# TRC1_0_0.net
KiCad netlist of a schematic drawn in EAGLE
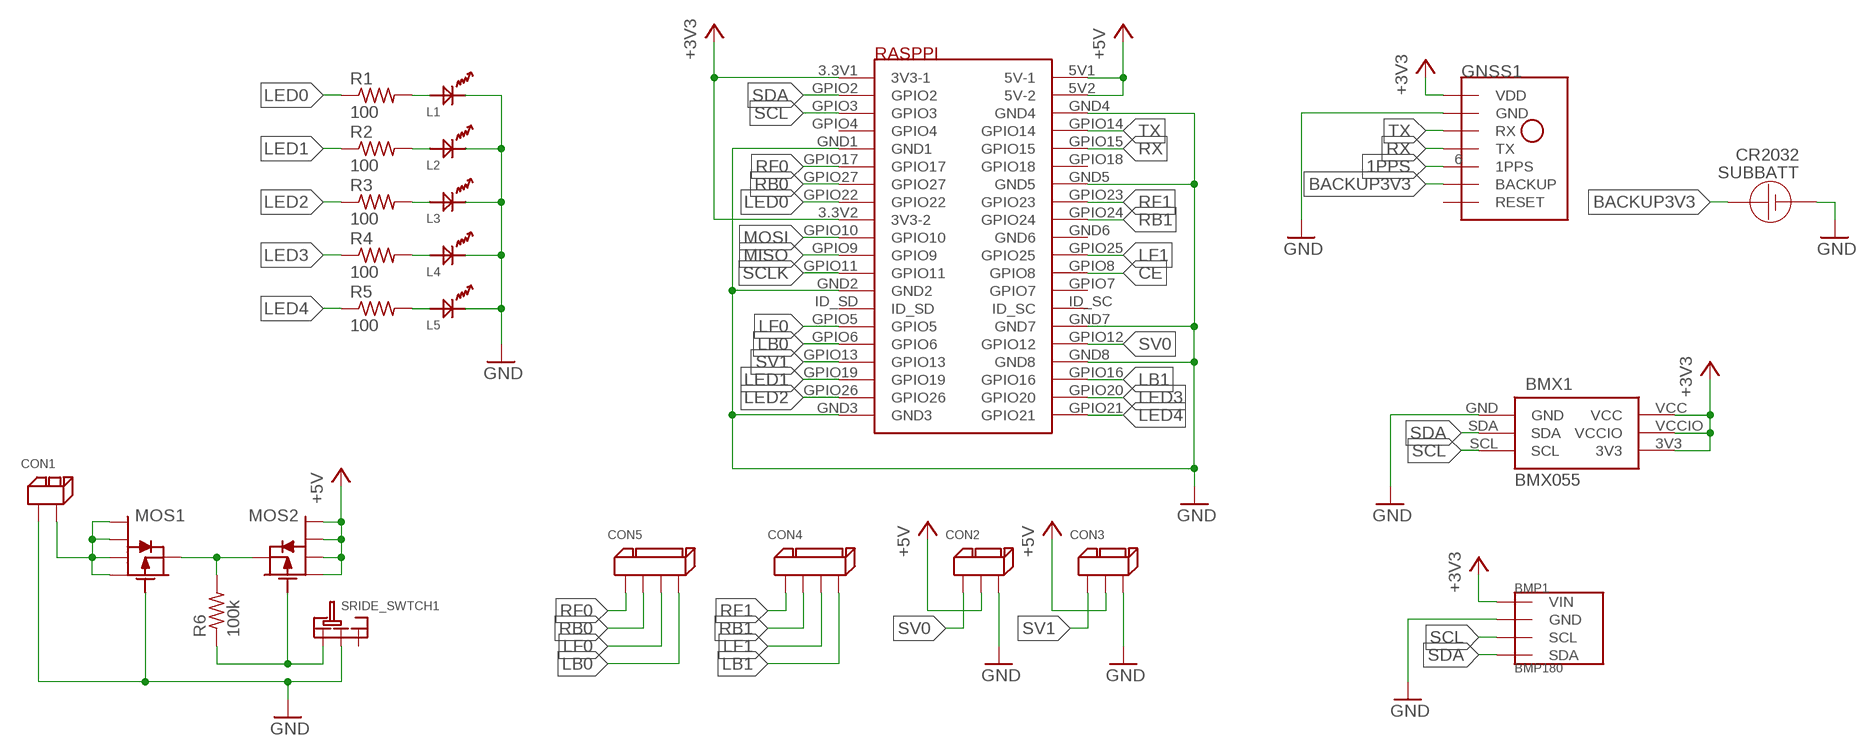
[diagram p0: schematic, sheet 1]

(export (version "E")
  (design (tool "Eeschema 10.0.6"))
  (components
    (comp (ref "BMP1")
      (value "BMP180")
      (footprint "eagle-import:GY-68")
      (libsource (lib "eagle-import") (part "BMP180"))
    )
    (comp (ref "BMX1")
      (value "BMX055")
      (footprint "eagle-import:BMX055")
      (libsource (lib "eagle-import") (part "BMX055"))
    )
    (comp (ref "CON1")
      (value "2PIN")
      (footprint "eagle-import:2PIN")
      (libsource (lib "eagle-import") (part "2PIN"))
    )
    (comp (ref "CON2")
      (value "3PIN")
      (footprint "eagle-import:3PIN")
      (libsource (lib "eagle-import") (part "3PIN"))
    )
    (comp (ref "CON3")
      (value "3PIN")
      (footprint "eagle-import:3PIN")
      (libsource (lib "eagle-import") (part "3PIN"))
    )
    (comp (ref "CON4")
      (value "4PIN")
      (footprint "eagle-import:4PIN")
      (libsource (lib "eagle-import") (part "4PIN"))
    )
    (comp (ref "CON5")
      (value "4PIN")
      (footprint "eagle-import:4PIN")
      (libsource (lib "eagle-import") (part "4PIN"))
    )
    (comp (ref "GNSS1")
      (value "GYSFDMAXB")
      (footprint "eagle-import:GYSFDMAXB")
      (libsource (lib "eagle-import") (part "GYSFDMAXB"))
    )
    (comp (ref "L1")
      (value "OSXX1608C1A")
      (footprint "eagle-import:OSXX1608C1A")
      (libsource (lib "eagle-import") (part "OSXX1608C1A"))
    )
    (comp (ref "L2")
      (value "OSXX1608C1A")
      (footprint "eagle-import:OSXX1608C1A")
      (libsource (lib "eagle-import") (part "OSXX1608C1A"))
    )
    (comp (ref "L3")
      (value "OSXX1608C1A")
      (footprint "eagle-import:OSXX1608C1A")
      (libsource (lib "eagle-import") (part "OSXX1608C1A"))
    )
    (comp (ref "L4")
      (value "OSXX1608C1A")
      (footprint "eagle-import:OSXX1608C1A")
      (libsource (lib "eagle-import") (part "OSXX1608C1A"))
    )
    (comp (ref "L5")
      (value "OSXX1608C1A")
      (footprint "eagle-import:OSXX1608C1A")
      (libsource (lib "eagle-import") (part "OSXX1608C1A"))
    )
    (comp (ref "MOS1")
      (value "PCH_SSM6J808R")
      (footprint "eagle-import:SSM6J808R")
      (libsource (lib "eagle-import") (part "PCH_SSM6J808R"))
    )
    (comp (ref "MOS2")
      (value "PCH_SSM6J808R")
      (footprint "eagle-import:SSM6J808R")
      (libsource (lib "eagle-import") (part "PCH_SSM6J808R"))
    )
    (comp (ref "R1")
      (value "100")
      (footprint "eagle-import:R0201")
      (libsource (lib "eagle-import") (part "R-US_R0201"))
    )
    (comp (ref "R2")
      (value "100")
      (footprint "eagle-import:R0201")
      (libsource (lib "eagle-import") (part "R-US_R0201"))
    )
    (comp (ref "R3")
      (value "100")
      (footprint "eagle-import:R0201")
      (libsource (lib "eagle-import") (part "R-US_R0201"))
    )
    (comp (ref "R4")
      (value "100")
      (footprint "eagle-import:R0201")
      (libsource (lib "eagle-import") (part "R-US_R0201"))
    )
    (comp (ref "R5")
      (value "100")
      (footprint "eagle-import:R0201")
      (libsource (lib "eagle-import") (part "R-US_R0201"))
    )
    (comp (ref "R6")
      (value "100k")
      (footprint "eagle-import:R0201")
      (libsource (lib "eagle-import") (part "R-US_R0201"))
    )
    (comp (ref "RASPPI")
      (value "RASPBERYPIZEROW")
      (footprint "eagle-import:RASPBERYPIZEROW")
      (libsource (lib "eagle-import") (part "RASPBERYPIZEROW"))
    )
    (comp (ref "SRIDE_SWTCH1")
      (value "SRIDE_SWITCH")
      (footprint "eagle-import:SRIDE_SWITCH")
      (libsource (lib "eagle-import") (part "SRIDE_SWITCH"))
    )
    (comp (ref "SUBBATT")
      (value "CR2032")
      (footprint "eagle-import:CR2032")
      (libsource (lib "eagle-import") (part "CR2032"))
    )
  )
  (nets
    (net (code "1") (name "+3V3") (class "Default")
      (node (ref "BMP1") (pin "P1") (pinfunction "VIN_P1") (pintype "bidirectional"))
      (node (ref "BMX1") (pin "3V3") (pinfunction "3V3_3V3") (pintype "power_in"))
      (node (ref "BMX1") (pin "VCC") (pinfunction "VCC_VCC") (pintype "power_in"))
      (node (ref "BMX1") (pin "VCCIO") (pinfunction "VCCIO_VCCIO") (pintype "power_in"))
      (node (ref "GNSS1") (pin "16") (pinfunction "VDD_16") (pintype "bidirectional"))
      (node (ref "RASPPI") (pin "3.3V1") (pinfunction "3V3-1_3.3V1") (pintype "bidirectional"))
      (node (ref "RASPPI") (pin "3.3V2") (pinfunction "3V3-2_3.3V2") (pintype "bidirectional"))
    )
    (net (code "2") (name "+5V") (class "Default")
      (node (ref "CON2") (pin "P$2") (pinfunction "P$2_P$2") (pintype "bidirectional"))
      (node (ref "CON3") (pin "P$2") (pinfunction "P$2_P$2") (pintype "bidirectional"))
      (node (ref "MOS2") (pin "1") (pinfunction "1_1") (pintype "bidirectional"))
      (node (ref "MOS2") (pin "2") (pinfunction "2_2") (pintype "bidirectional"))
      (node (ref "MOS2") (pin "5") (pinfunction "5_5") (pintype "bidirectional"))
      (node (ref "MOS2") (pin "6") (pinfunction "6_6") (pintype "bidirectional"))
      (node (ref "RASPPI") (pin "5V1") (pinfunction "5V-1_5V1") (pintype "bidirectional"))
      (node (ref "RASPPI") (pin "5V2") (pinfunction "5V-2_5V2") (pintype "bidirectional"))
    )
    (net (code "3") (name "1PPS") (class "Default")
      (node (ref "GNSS1") (pin "6") (pinfunction "1PPS_6") (pintype "bidirectional"))
    )
    (net (code "4") (name "BACKUP3V3") (class "Default")
      (node (ref "GNSS1") (pin "14") (pinfunction "BACKUP_14") (pintype "bidirectional"))
      (node (ref "SUBBATT") (pin "VCC") (pinfunction "VCC_VCC") (pintype "bidirectional"))
      (node (ref "SUBBATT") (pin "VCC2") (pinfunction "VCC_VCC2") (pintype "bidirectional"))
    )
    (net (code "5") (name "CE") (class "Default")
      (node (ref "RASPPI") (pin "GPIO8") (pinfunction "GPIO8_GPIO8") (pintype "bidirectional"))
    )
    (net (code "6") (name "GND") (class "Default")
      (node (ref "BMP1") (pin "P2") (pinfunction "GND_P2") (pintype "bidirectional"))
      (node (ref "BMX1") (pin "GND") (pinfunction "GND_GND") (pintype "power_in"))
      (node (ref "CON1") (pin "P$1") (pinfunction "P$1_P$1") (pintype "bidirectional"))
      (node (ref "CON2") (pin "P$3") (pinfunction "P$3_P$3") (pintype "bidirectional"))
      (node (ref "CON3") (pin "P$3") (pinfunction "P$3_P$3") (pintype "bidirectional"))
      (node (ref "GNSS1") (pin "1") (pinfunction "GND_1") (pintype "bidirectional"))
      (node (ref "GNSS1") (pin "10") (pinfunction "GND_10") (pintype "bidirectional"))
      (node (ref "GNSS1") (pin "12") (pinfunction "GND_12") (pintype "bidirectional"))
      (node (ref "GNSS1") (pin "19") (pinfunction "GND_19") (pintype "bidirectional"))
      (node (ref "GNSS1") (pin "2") (pinfunction "GND_2") (pintype "bidirectional"))
      (node (ref "GNSS1") (pin "20") (pinfunction "GND_20") (pintype "bidirectional"))
      (node (ref "GNSS1") (pin "7") (pinfunction "GND_7") (pintype "bidirectional"))
      (node (ref "L1") (pin "CT") (pinfunction "CT_CT") (pintype "bidirectional"))
      (node (ref "L2") (pin "CT") (pinfunction "CT_CT") (pintype "bidirectional"))
      (node (ref "L3") (pin "CT") (pinfunction "CT_CT") (pintype "bidirectional"))
      (node (ref "L4") (pin "CT") (pinfunction "CT_CT") (pintype "bidirectional"))
      (node (ref "L5") (pin "CT") (pinfunction "CT_CT") (pintype "bidirectional"))
      (node (ref "MOS1") (pin "3") (pinfunction "3_3") (pintype "bidirectional"))
      (node (ref "RASPPI") (pin "GND1") (pinfunction "GND1_GND1") (pintype "bidirectional"))
      (node (ref "RASPPI") (pin "GND2") (pinfunction "GND2_GND2") (pintype "bidirectional"))
      (node (ref "RASPPI") (pin "GND3") (pinfunction "GND3_GND3") (pintype "bidirectional"))
      (node (ref "RASPPI") (pin "GND4") (pinfunction "GND4_GND4") (pintype "bidirectional"))
      (node (ref "RASPPI") (pin "GND5") (pinfunction "GND5_GND5") (pintype "bidirectional"))
      (node (ref "RASPPI") (pin "GND7") (pinfunction "GND7_GND7") (pintype "bidirectional"))
      (node (ref "RASPPI") (pin "GND8") (pinfunction "GND8_GND8") (pintype "bidirectional"))
      (node (ref "SRIDE_SWTCH1") (pin "LR") (pinfunction "LR_LR") (pintype "bidirectional"))
      (node (ref "SUBBATT") (pin "GND") (pinfunction "GND_GND") (pintype "bidirectional"))
    )
    (net (code "7") (name "LB0") (class "Default")
      (node (ref "CON5") (pin "P$4") (pinfunction "P$4_P$4") (pintype "bidirectional"))
      (node (ref "RASPPI") (pin "GPIO6") (pinfunction "GPIO6_GPIO6") (pintype "bidirectional"))
    )
    (net (code "8") (name "LB1") (class "Default")
      (node (ref "CON4") (pin "P$4") (pinfunction "P$4_P$4") (pintype "bidirectional"))
      (node (ref "RASPPI") (pin "GPIO16") (pinfunction "GPIO16_GPIO16") (pintype "bidirectional"))
    )
    (net (code "9") (name "LED0") (class "Default")
      (node (ref "R1") (pin "1") (pinfunction "1_1") (pintype "passive"))
      (node (ref "RASPPI") (pin "GPIO22") (pinfunction "GPIO22_GPIO22") (pintype "bidirectional"))
    )
    (net (code "10") (name "LED1") (class "Default")
      (node (ref "R2") (pin "1") (pinfunction "1_1") (pintype "passive"))
      (node (ref "RASPPI") (pin "GPIO19") (pinfunction "GPIO19_GPIO19") (pintype "bidirectional"))
    )
    (net (code "11") (name "LED2") (class "Default")
      (node (ref "R3") (pin "1") (pinfunction "1_1") (pintype "passive"))
      (node (ref "RASPPI") (pin "GPIO26") (pinfunction "GPIO26_GPIO26") (pintype "bidirectional"))
    )
    (net (code "12") (name "LED3") (class "Default")
      (node (ref "R4") (pin "1") (pinfunction "1_1") (pintype "passive"))
      (node (ref "RASPPI") (pin "GPIO20") (pinfunction "GPIO20_GPIO20") (pintype "bidirectional"))
    )
    (net (code "13") (name "LED4") (class "Default")
      (node (ref "R5") (pin "1") (pinfunction "1_1") (pintype "passive"))
      (node (ref "RASPPI") (pin "GPIO21") (pinfunction "GPIO21_GPIO21") (pintype "bidirectional"))
    )
    (net (code "14") (name "LF0") (class "Default")
      (node (ref "CON5") (pin "P$3") (pinfunction "P$3_P$3") (pintype "bidirectional"))
      (node (ref "RASPPI") (pin "GPIO5") (pinfunction "GPIO5_GPIO5") (pintype "bidirectional"))
    )
    (net (code "15") (name "LF1") (class "Default")
      (node (ref "CON4") (pin "P$3") (pinfunction "P$3_P$3") (pintype "bidirectional"))
      (node (ref "RASPPI") (pin "GPIO25") (pinfunction "GPIO25_GPIO25") (pintype "bidirectional"))
    )
    (net (code "16") (name "MISO") (class "Default")
      (node (ref "RASPPI") (pin "GPIO9") (pinfunction "GPIO9_GPIO9") (pintype "bidirectional"))
    )
    (net (code "17") (name "MOSI") (class "Default")
      (node (ref "RASPPI") (pin "GPIO10") (pinfunction "GPIO10_GPIO10") (pintype "bidirectional"))
    )
    (net (code "18") (name "Net-(CON1-PadP$2)") (class "Default")
      (node (ref "CON1") (pin "P$2") (pinfunction "P$2_P$2") (pintype "bidirectional"))
      (node (ref "MOS1") (pin "1") (pinfunction "1_1") (pintype "bidirectional"))
      (node (ref "MOS1") (pin "2") (pinfunction "2_2") (pintype "bidirectional"))
      (node (ref "MOS1") (pin "5") (pinfunction "5_5") (pintype "bidirectional"))
      (node (ref "MOS1") (pin "6") (pinfunction "6_6") (pintype "bidirectional"))
    )
    (net (code "19") (name "Net-(L1-PadAN)") (class "Default")
      (node (ref "L1") (pin "AN") (pinfunction "AN_AN") (pintype "bidirectional"))
      (node (ref "R1") (pin "2") (pinfunction "2_2") (pintype "passive"))
    )
    (net (code "20") (name "Net-(L2-PadAN)") (class "Default")
      (node (ref "L2") (pin "AN") (pinfunction "AN_AN") (pintype "bidirectional"))
      (node (ref "R2") (pin "2") (pinfunction "2_2") (pintype "passive"))
    )
    (net (code "21") (name "Net-(L3-PadAN)") (class "Default")
      (node (ref "L3") (pin "AN") (pinfunction "AN_AN") (pintype "bidirectional"))
      (node (ref "R3") (pin "2") (pinfunction "2_2") (pintype "passive"))
    )
    (net (code "22") (name "Net-(L4-PadAN)") (class "Default")
      (node (ref "L4") (pin "AN") (pinfunction "AN_AN") (pintype "bidirectional"))
      (node (ref "R4") (pin "2") (pinfunction "2_2") (pintype "passive"))
    )
    (net (code "23") (name "Net-(L5-PadAN)") (class "Default")
      (node (ref "L5") (pin "AN") (pinfunction "AN_AN") (pintype "bidirectional"))
      (node (ref "R5") (pin "2") (pinfunction "2_2") (pintype "passive"))
    )
    (net (code "24") (name "Net-(MOS1-Pad4)") (class "Default")
      (node (ref "MOS1") (pin "4") (pinfunction "4_4") (pintype "bidirectional"))
      (node (ref "MOS2") (pin "4") (pinfunction "4_4") (pintype "bidirectional"))
      (node (ref "R6") (pin "2") (pinfunction "2_2") (pintype "passive"))
    )
    (net (code "25") (name "Net-(MOS2-Pad3)") (class "Default")
      (node (ref "MOS2") (pin "3") (pinfunction "3_3") (pintype "bidirectional"))
      (node (ref "R6") (pin "1") (pinfunction "1_1") (pintype "passive"))
      (node (ref "SRIDE_SWTCH1") (pin "L") (pinfunction "L_L") (pintype "bidirectional"))
    )
    (net (code "26") (name "RB0") (class "Default")
      (node (ref "CON5") (pin "P$2") (pinfunction "P$2_P$2") (pintype "bidirectional"))
      (node (ref "RASPPI") (pin "GPIO27") (pinfunction "GPIO27_GPIO27") (pintype "bidirectional"))
    )
    (net (code "27") (name "RB1") (class "Default")
      (node (ref "CON4") (pin "P$2") (pinfunction "P$2_P$2") (pintype "bidirectional"))
      (node (ref "RASPPI") (pin "GPIO24") (pinfunction "GPIO24_GPIO24") (pintype "bidirectional"))
    )
    (net (code "28") (name "RF0") (class "Default")
      (node (ref "CON5") (pin "P$1") (pinfunction "P$1_P$1") (pintype "bidirectional"))
      (node (ref "RASPPI") (pin "GPIO17") (pinfunction "GPIO17_GPIO17") (pintype "bidirectional"))
    )
    (net (code "29") (name "RF1") (class "Default")
      (node (ref "CON4") (pin "P$1") (pinfunction "P$1_P$1") (pintype "bidirectional"))
      (node (ref "RASPPI") (pin "GPIO23") (pinfunction "GPIO23_GPIO23") (pintype "bidirectional"))
    )
    (net (code "30") (name "RX") (class "Default")
      (node (ref "GNSS1") (pin "5") (pinfunction "TX_5") (pintype "bidirectional"))
      (node (ref "RASPPI") (pin "GPIO15") (pinfunction "GPIO15_GPIO15") (pintype "bidirectional"))
    )
    (net (code "31") (name "SCL") (class "Default")
      (node (ref "BMP1") (pin "P3") (pinfunction "SCL_P3") (pintype "bidirectional"))
      (node (ref "BMX1") (pin "SCL") (pinfunction "SCL_SCL") (pintype "bidirectional"))
      (node (ref "RASPPI") (pin "GPIO3") (pinfunction "GPIO3_GPIO3") (pintype "bidirectional"))
    )
    (net (code "32") (name "SCLK") (class "Default")
      (node (ref "RASPPI") (pin "GPIO11") (pinfunction "GPIO11_GPIO11") (pintype "bidirectional"))
    )
    (net (code "33") (name "SDA") (class "Default")
      (node (ref "BMP1") (pin "P4") (pinfunction "SDA_P4") (pintype "bidirectional"))
      (node (ref "BMX1") (pin "SDA") (pinfunction "SDA_SDA") (pintype "bidirectional"))
      (node (ref "RASPPI") (pin "GPIO2") (pinfunction "GPIO2_GPIO2") (pintype "bidirectional"))
    )
    (net (code "34") (name "SV0") (class "Default")
      (node (ref "CON2") (pin "P$1") (pinfunction "P$1_P$1") (pintype "bidirectional"))
      (node (ref "RASPPI") (pin "GPIO12") (pinfunction "GPIO12_GPIO12") (pintype "bidirectional"))
    )
    (net (code "35") (name "SV1") (class "Default")
      (node (ref "CON3") (pin "P$1") (pinfunction "P$1_P$1") (pintype "bidirectional"))
      (node (ref "RASPPI") (pin "GPIO13") (pinfunction "GPIO13_GPIO13") (pintype "bidirectional"))
    )
    (net (code "36") (name "TX") (class "Default")
      (node (ref "GNSS1") (pin "3") (pinfunction "RX_3") (pintype "bidirectional"))
      (node (ref "RASPPI") (pin "GPIO14") (pinfunction "GPIO14_GPIO14") (pintype "bidirectional"))
    )
    (net (code "37") (name "unconnected-(GNSS1-RESET-Pad4)") (class "Default")
      (node (ref "GNSS1") (pin "4") (pinfunction "RESET_4") (pintype "bidirectional"))
    )
    (net (code "38") (name "unconnected-(RASPPI-PadGND6)") (class "Default")
      (node (ref "RASPPI") (pin "GND6") (pinfunction "GND6_GND6") (pintype "bidirectional"))
    )
    (net (code "39") (name "unconnected-(RASPPI-PadGPIO4)") (class "Default")
      (node (ref "RASPPI") (pin "GPIO4") (pinfunction "GPIO4_GPIO4") (pintype "bidirectional"))
    )
    (net (code "40") (name "unconnected-(RASPPI-PadGPIO7)") (class "Default")
      (node (ref "RASPPI") (pin "GPIO7") (pinfunction "GPIO7_GPIO7") (pintype "bidirectional"))
    )
    (net (code "41") (name "unconnected-(RASPPI-PadGPIO18)") (class "Default")
      (node (ref "RASPPI") (pin "GPIO18") (pinfunction "GPIO18_GPIO18") (pintype "bidirectional"))
    )
    (net (code "42") (name "unconnected-(RASPPI-PadID_SC)") (class "Default")
      (node (ref "RASPPI") (pin "ID_SC") (pinfunction "ID_SC_ID_SC") (pintype "bidirectional"))
    )
    (net (code "43") (name "unconnected-(RASPPI-PadID_SD)") (class "Default")
      (node (ref "RASPPI") (pin "ID_SD") (pinfunction "ID_SD_ID_SD") (pintype "bidirectional"))
    )
    (net (code "44") (name "unconnected-(SRIDE_SWTCH1-PadR)") (class "Default")
      (node (ref "SRIDE_SWTCH1") (pin "R") (pinfunction "R_R") (pintype "bidirectional"))
    )
  )
)
